# YosanoLoveButton.net
KiCad netlist of a schematic drawn in EAGLE
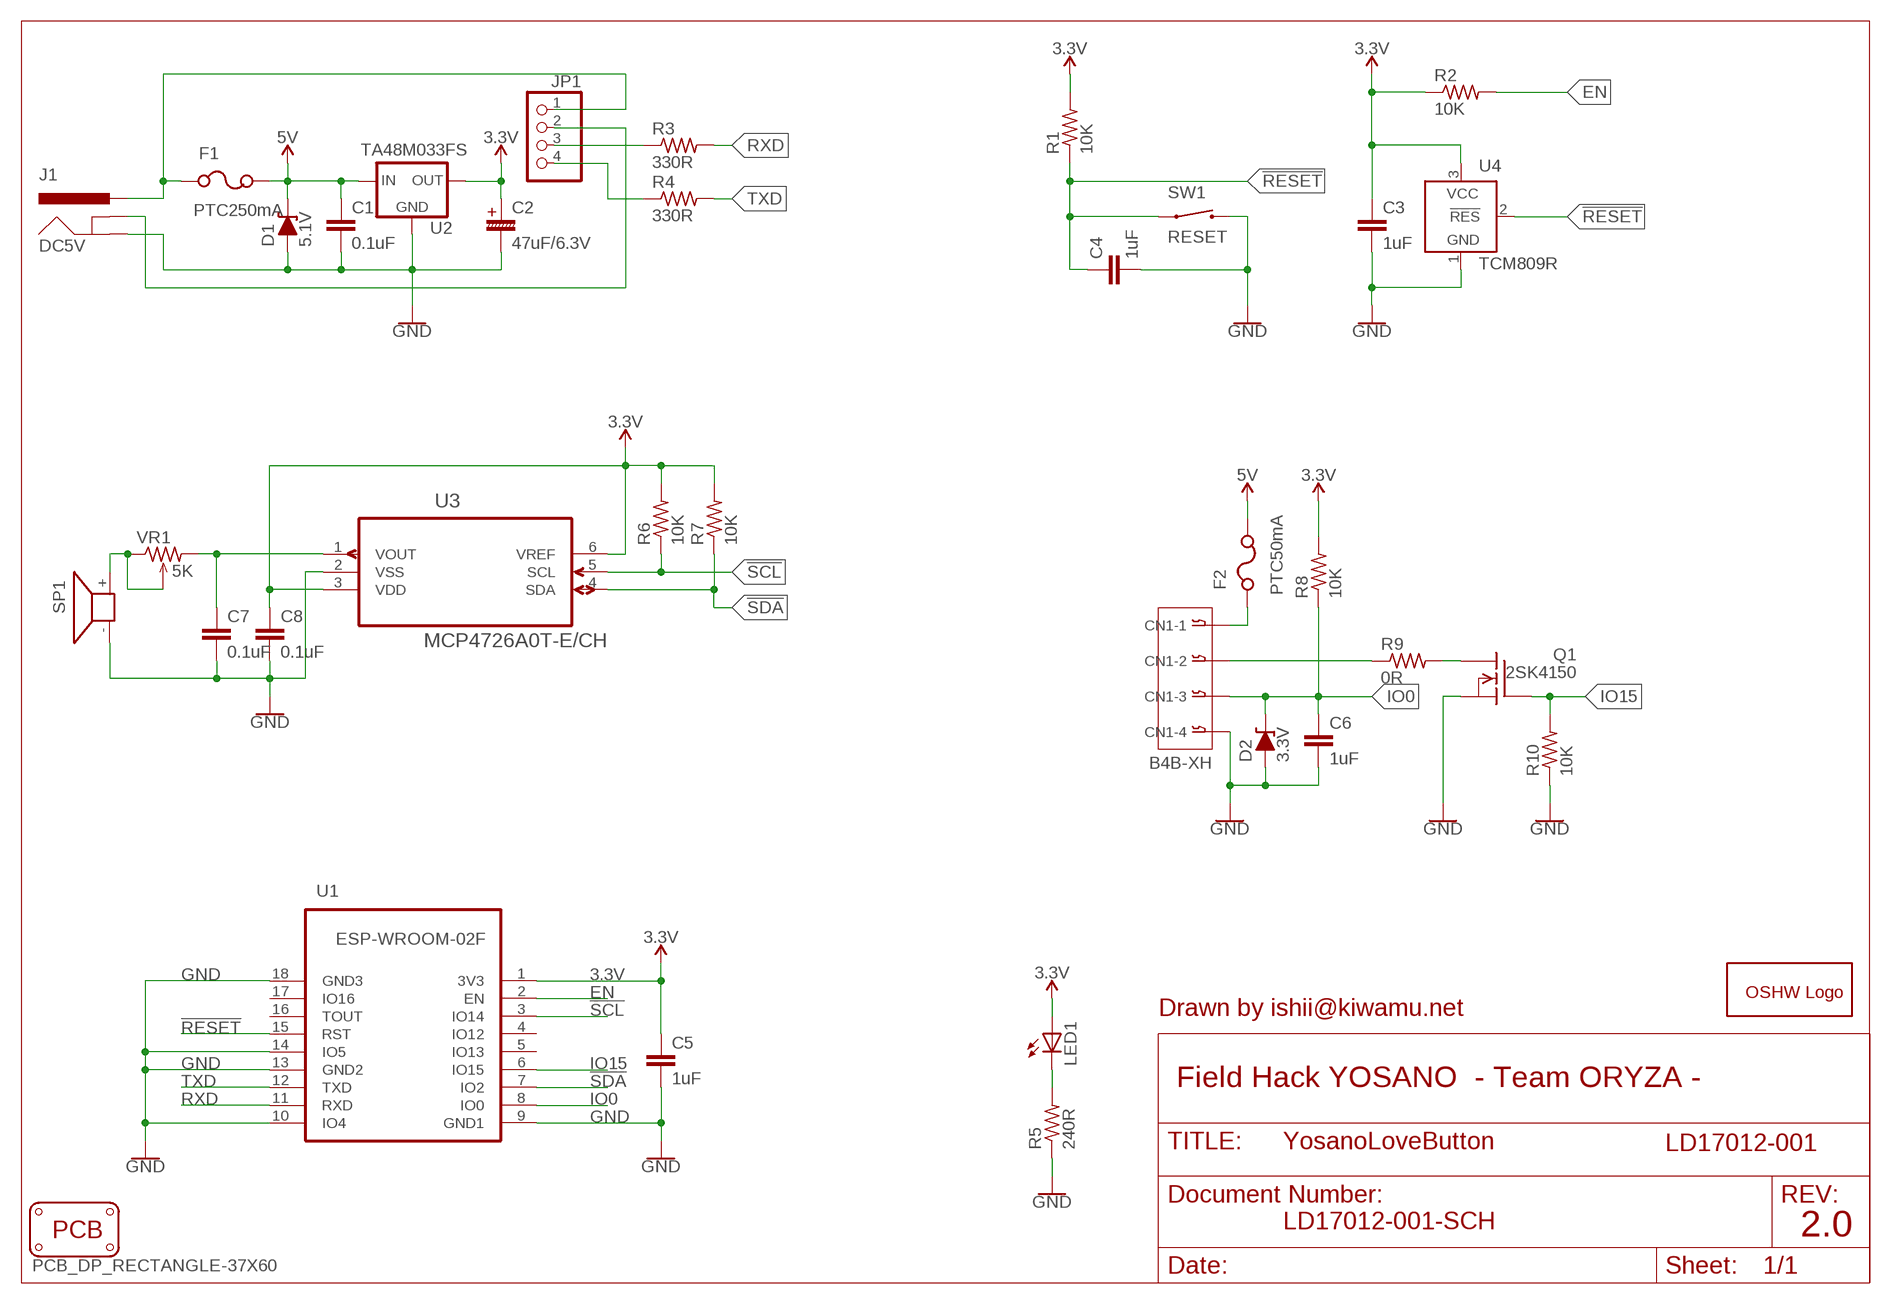
[diagram p0: schematic, sheet 1]

(export (version "E")
  (design (tool "Eeschema 10.0.6"))
  (components
    (comp (ref "C1")
      (value "0.1uF")
      (footprint "eagle-import:C5B2.5")
      (fields (field (name "MF") "株式会社村田製作所(muRata)") (field (name "MPN") "RDER72E104K2K1H03B"))
      (libsource (lib "eagle-import") (part "C5/2.5"))
    )
    (comp (ref "C2")
      (value "47uF/6.3V")
      (footprint "eagle-import:E2,0-5")
      (fields (field (name "MF") "東信工業") (field (name "MPN") "0JUTCX470M"))
      (libsource (lib "eagle-import") (part "C-PR-2,0X5"))
    )
    (comp (ref "C3")
      (value "1uF")
      (footprint "eagle-import:C5B2.5")
      (fields (field (name "MF") "株式会社村田製作所(muRata)") (field (name "MPN") "RDER71H105K2K1H03B"))
      (libsource (lib "eagle-import") (part "C5/2.5"))
    )
    (comp (ref "C4")
      (value "1uF")
      (footprint "eagle-import:C5B2.5")
      (fields (field (name "MF") "株式会社村田製作所(muRata)") (field (name "MPN") "RDER71H105K2K1H03B"))
      (libsource (lib "eagle-import") (part "C5/2.5"))
    )
    (comp (ref "C5")
      (value "1uF")
      (footprint "eagle-import:C5B2.5")
      (fields (field (name "MF") "株式会社村田製作所(muRata)") (field (name "MPN") "RDER71H105K2K1H03B"))
      (libsource (lib "eagle-import") (part "C5/2.5"))
    )
    (comp (ref "C6")
      (value "1uF")
      (footprint "eagle-import:C5B2.5")
      (fields (field (name "MF") "株式会社村田製作所(muRata)") (field (name "MPN") "RDER71H105K2K1H03B"))
      (libsource (lib "eagle-import") (part "C5/2.5"))
    )
    (comp (ref "C7")
      (value "0.1uF")
      (footprint "eagle-import:C5B2.5")
      (fields (field (name "MF") "株式会社村田製作所(muRata)") (field (name "MPN") "RDER72E104K2K1H03B"))
      (libsource (lib "eagle-import") (part "C5/2.5"))
    )
    (comp (ref "C8")
      (value "0.1uF")
      (footprint "eagle-import:C5B2.5")
      (fields (field (name "MF") "株式会社村田製作所(muRata)") (field (name "MPN") "RDER72E104K2K1H03B"))
      (libsource (lib "eagle-import") (part "C5/2.5"))
    )
    (comp (ref "CN1")
      (value "B4B-XH")
      (footprint "eagle-import:B4B-XH")
      (fields (field (name "MF") "日本圧着端子製造(JST)") (field (name "MPN") "B4B-XH-A(LF)(SN)"))
      (libsource (lib "eagle-import") (part "04-JST-B4B-XH-A"))
    )
    (comp (ref "D1")
      (value "5.1V")
      (footprint "eagle-import:ZDIO-5-LD")
      (fields (field (name "MF") "PANJIT") (field (name "MPN") "GDZJ5.1B"))
      (libsource (lib "eagle-import") (part "ZENER-DIODEZD-5LD"))
    )
    (comp (ref "D2")
      (value "3.3V")
      (footprint "eagle-import:ZDIO-5-LD")
      (fields (field (name "MF") "PANJIT") (field (name "MPN") "GDZJ3.3B"))
      (libsource (lib "eagle-import") (part "ZENER-DIODEZD-5LD"))
    )
    (comp (ref "F1")
      (value "PTC250mA")
      (footprint "eagle-import:PTC-PTH")
      (fields (field (name "MF") "Tyco Electronics Corporation") (field (name "MPN") "RXEF005"))
      (libsource (lib "eagle-import") (part "PTCPTH"))
    )
    (comp (ref "F2")
      (value "PTC50mA")
      (footprint "eagle-import:PTC-PTH")
      (fields (field (name "MF") "Tyco Electronics Corporation") (field (name "MPN") "RXEF005"))
      (libsource (lib "eagle-import") (part "PTCPTH"))
    )
    (comp (ref "GOLD_ORB_SM1")
      (value "OSHWLOGOLOGO5MM")
      (footprint "eagle-import:OSHW_5MM")
      (libsource (lib "eagle-import") (part "OSHWLOGOLOGO5MM"))
    )
    (comp (ref "J1")
      (value "DC5V")
      (footprint "eagle-import:POWER_JACK_PTH")
      (fields (field (name "MF") "マル信無線電機株式会社") (field (name "MPN") "MJ-179P"))
      (libsource (lib "eagle-import") (part "POWER_JACK"))
    )
    (comp (ref "JP1")
      (value "PINHD-1X4")
      (footprint "eagle-import:1X04")
      (fields (field (name "MF") "Useconn Electronics Ltd.") (field (name "MPN") "PHA-1x4SG"))
      (libsource (lib "eagle-import") (part "PINHD-1X4"))
    )
    (comp (ref "LED1")
      (value "LED3MM")
      (footprint "eagle-import:LED3MM")
      (fields (field (name "MF") "OptoSupply") (field (name "MPN") "OSR5JA3Z74A"))
      (libsource (lib "eagle-import") (part "LED3MM"))
    )
    (comp (ref "PCB1")
      (value "PCB_DP_RECTANGLE-37X60")
      (footprint "eagle-import:DP6037_V1")
      (libsource (lib "eagle-import") (part "PCB_DP_RECTANGLE-37X60"))
    )
    (comp (ref "Q1")
      (value "2SK4150")
      (footprint "eagle-import:TO92")
      (fields (field (name "MF") "RENESAS") (field (name "MPN") "2SK4150TZ-E"))
      (libsource (lib "eagle-import") (part "2SK4150"))
    )
    (comp (ref "R1")
      (value "10K")
      (footprint "eagle-import:0204_5")
      (fields (field (name "MF") "タクマン") (field (name "MPN") "RD25SJ10K"))
      (libsource (lib "eagle-import") (part "R-US_0204/5"))
    )
    (comp (ref "R2")
      (value "10K")
      (footprint "eagle-import:0204_5")
      (fields (field (name "MF") "タクマン") (field (name "MPN") "RD25SJ10K"))
      (libsource (lib "eagle-import") (part "R-US_0204/5"))
    )
    (comp (ref "R3")
      (value "330R")
      (footprint "eagle-import:0204_5")
      (fields (field (name "MF") "タクマン") (field (name "MPN") "RD25SJ330R"))
      (libsource (lib "eagle-import") (part "R-US_0204/5"))
    )
    (comp (ref "R4")
      (value "330R")
      (footprint "eagle-import:0204_5")
      (fields (field (name "MF") "タクマン") (field (name "MPN") "RD25SJ300R"))
      (libsource (lib "eagle-import") (part "R-US_0204/5"))
    )
    (comp (ref "R5")
      (value "240R")
      (footprint "eagle-import:0204_5")
      (fields (field (name "MF") "タクマン") (field (name "MPN") "RD25SJ 240R"))
      (libsource (lib "eagle-import") (part "R-US_0204/5"))
    )
    (comp (ref "R6")
      (value "10K")
      (footprint "eagle-import:0204_5")
      (fields (field (name "MF") "タクマン") (field (name "MPN") "RD25SJ10K"))
      (libsource (lib "eagle-import") (part "R-US_0204/5"))
    )
    (comp (ref "R7")
      (value "10K")
      (footprint "eagle-import:0204_5")
      (fields (field (name "MF") "タクマン") (field (name "MPN") "RD25SJ10K"))
      (libsource (lib "eagle-import") (part "R-US_0204/5"))
    )
    (comp (ref "R8")
      (value "10K")
      (footprint "eagle-import:0204_5")
      (fields (field (name "MF") "タクマン") (field (name "MPN") "RD25SJ10K"))
      (libsource (lib "eagle-import") (part "R-US_0204/5"))
    )
    (comp (ref "R9")
      (value "0R")
      (footprint "eagle-import:0204_5")
      (fields (field (name "MF") "タクマン") (field (name "MPN") "RD25SP 0R"))
      (libsource (lib "eagle-import") (part "R-US_0204/5"))
    )
    (comp (ref "R10")
      (value "10K")
      (footprint "eagle-import:0204_5")
      (fields (field (name "MF") "タクマン") (field (name "MPN") "RD25SJ10K"))
      (libsource (lib "eagle-import") (part "R-US_0204/5"))
    )
    (comp (ref "SP1")
      (value "PKM13EPYH4000")
      (footprint "eagle-import:PKM13EPYH4000")
      (fields (field (name "MF") "muRata"))
      (libsource (lib "eagle-import") (part "PKM13EPYH4000"))
    )
    (comp (ref "SW1")
      (value "RESET")
      (footprint "eagle-import:TVBP06")
      (fields
        (field (name "MF") "Zhejiang Jianfu Electronics Co., Ltd")
        (field (name "MPN") "TVBP06-B043CB-B")
      )
      (libsource (lib "eagle-import") (part "TVBP06"))
    )
    (comp (ref "U1")
      (value "ESP-WROOM-02F")
      (footprint "eagle-import:FRONT-FACE")
      (fields (field (name "MF") "Espressif") (field (name "MPN") "ESP-WROOM-02"))
      (libsource (lib "eagle-import") (part "ESP-WROOM-02F"))
    )
    (comp (ref "U2")
      (value "TA48M033FS")
      (footprint "eagle-import:HSIP3")
      (fields (field (name "MF") "株式会社東芝セミコンダクター社(TOSHIBA)") (field (name "MPN") "TA48M033F(S Q)"))
      (libsource (lib "eagle-import") (part "TA48MS033F"))
    )
    (comp (ref "U3")
      (value "MCP4726A0T-E/CH")
      (footprint "eagle-import:SOT95P270X145-6N")
      (fields (field (name "MF") "Microchip") (field (name "MPN") "MCP4725A0T-E/CH"))
      (libsource (lib "eagle-import") (part "MCP4726A0T-E/CH"))
    )
    (comp (ref "U4")
      (value "TCM809R")
      (footprint "eagle-import:SOT23B-3")
      (fields (field (name "MF") "MICROCHIP") (field (name "MPN") "TCM809MENB713"))
      (libsource (lib "eagle-import") (part "TCM809"))
    )
    (comp (ref "VR1")
      (value "5K")
      (footprint "eagle-import:3362P")
      (fields (field (name "MF") "bourns"))
      (libsource (lib "eagle-import") (part "3362P"))
    )
  )
  (nets
    (net (code "1") (name "/~{RESET}") (class "Default")
      (node (ref "C4") (pin "1") (pinfunction "1_1") (pintype "passive"))
      (node (ref "R1") (pin "1") (pinfunction "1_1") (pintype "passive"))
      (node (ref "SW1") (pin "1") (pinfunction "1_1") (pintype "passive"))
      (node (ref "U1") (pin "15") (pinfunction "RST_15") (pintype "bidirectional"))
      (node (ref "U4") (pin "2") (pinfunction "~{RES}_2") (pintype "output"))
    )
    (net (code "2") (name "/~{SCL}") (class "Default")
      (node (ref "R6") (pin "1") (pinfunction "1_1") (pintype "passive"))
      (node (ref "U1") (pin "3") (pinfunction "IO14_3") (pintype "bidirectional"))
      (node (ref "U3") (pin "5") (pinfunction "SCL_5") (pintype "input"))
    )
    (net (code "3") (name "/~{SDA}") (class "Default")
      (node (ref "R7") (pin "1") (pinfunction "1_1") (pintype "passive"))
      (node (ref "U1") (pin "7") (pinfunction "IO2_7") (pintype "bidirectional"))
      (node (ref "U3") (pin "4") (pinfunction "SDA_4") (pintype "bidirectional"))
    )
    (net (code "4") (name "3.3V") (class "Default")
      (node (ref "C2") (pin "+") (pinfunction "+_+") (pintype "passive"))
      (node (ref "C3") (pin "1") (pinfunction "1_1") (pintype "passive"))
      (node (ref "C5") (pin "1") (pinfunction "1_1") (pintype "passive"))
      (node (ref "C8") (pin "1") (pinfunction "1_1") (pintype "passive"))
      (node (ref "LED1") (pin "A") (pinfunction "A_A") (pintype "passive"))
      (node (ref "R1") (pin "2") (pinfunction "2_2") (pintype "passive"))
      (node (ref "R2") (pin "1") (pinfunction "1_1") (pintype "passive"))
      (node (ref "R6") (pin "2") (pinfunction "2_2") (pintype "passive"))
      (node (ref "R7") (pin "2") (pinfunction "2_2") (pintype "passive"))
      (node (ref "R8") (pin "2") (pinfunction "2_2") (pintype "passive"))
      (node (ref "U1") (pin "1") (pinfunction "3V3_1") (pintype "power_in"))
      (node (ref "U2") (pin "P$2") (pinfunction "OUT_P$2") (pintype "passive"))
      (node (ref "U3") (pin "3") (pinfunction "VDD_3") (pintype "power_in"))
      (node (ref "U3") (pin "6") (pinfunction "VREF_6") (pintype "power_in"))
      (node (ref "U4") (pin "3") (pinfunction "VCC_3") (pintype "power_in"))
    )
    (net (code "5") (name "5V") (class "Default")
      (node (ref "C1") (pin "1") (pinfunction "1_1") (pintype "passive"))
      (node (ref "D1") (pin "C") (pinfunction "C_C") (pintype "passive"))
      (node (ref "F1") (pin "2") (pinfunction "2_2") (pintype "bidirectional"))
      (node (ref "F2") (pin "2") (pinfunction "2_2") (pintype "bidirectional"))
      (node (ref "U2") (pin "P$1") (pinfunction "IN_P$1") (pintype "input"))
    )
    (net (code "6") (name "EN") (class "Default")
      (node (ref "R2") (pin "2") (pinfunction "2_2") (pintype "passive"))
      (node (ref "U1") (pin "2") (pinfunction "EN_2") (pintype "bidirectional"))
    )
    (net (code "7") (name "GND") (class "Default")
      (node (ref "C1") (pin "2") (pinfunction "2_2") (pintype "passive"))
      (node (ref "C2") (pin "-") (pinfunction "-_-") (pintype "passive"))
      (node (ref "C3") (pin "2") (pinfunction "2_2") (pintype "passive"))
      (node (ref "C4") (pin "2") (pinfunction "2_2") (pintype "passive"))
      (node (ref "C5") (pin "2") (pinfunction "2_2") (pintype "passive"))
      (node (ref "C6") (pin "2") (pinfunction "2_2") (pintype "passive"))
      (node (ref "C7") (pin "2") (pinfunction "2_2") (pintype "passive"))
      (node (ref "C8") (pin "2") (pinfunction "2_2") (pintype "passive"))
      (node (ref "CN1") (pin "P$4") (pinfunction "1_P$4") (pintype "passive"))
      (node (ref "D1") (pin "A") (pinfunction "A_A") (pintype "passive"))
      (node (ref "D2") (pin "A") (pinfunction "A_A") (pintype "passive"))
      (node (ref "J1") (pin "GND") (pinfunction "GND_GND") (pintype "bidirectional"))
      (node (ref "Q1") (pin "1") (pinfunction "S_1") (pintype "passive"))
      (node (ref "R10") (pin "1") (pinfunction "1_1") (pintype "passive"))
      (node (ref "R5") (pin "1") (pinfunction "1_1") (pintype "passive"))
      (node (ref "SP1") (pin "-") (pinfunction "2_-") (pintype "passive"))
      (node (ref "SW1") (pin "2") (pinfunction "2_2") (pintype "passive"))
      (node (ref "U1") (pin "10") (pinfunction "IO4_10") (pintype "bidirectional"))
      (node (ref "U1") (pin "13") (pinfunction "GND2_13") (pintype "power_in"))
      (node (ref "U1") (pin "14") (pinfunction "IO5_14") (pintype "open_collector"))
      (node (ref "U1") (pin "18") (pinfunction "GND3_18") (pintype "power_in"))
      (node (ref "U1") (pin "9") (pinfunction "GND1_9") (pintype "power_in"))
      (node (ref "U2") (pin "P$3") (pinfunction "GND_P$3") (pintype "power_in"))
      (node (ref "U3") (pin "2") (pinfunction "VSS_2") (pintype "power_in"))
      (node (ref "U4") (pin "1") (pinfunction "GND_1") (pintype "power_in"))
    )
    (net (code "8") (name "IO0") (class "Default")
      (node (ref "C6") (pin "1") (pinfunction "1_1") (pintype "passive"))
      (node (ref "CN1") (pin "P$3") (pinfunction "1_P$3") (pintype "passive"))
      (node (ref "D2") (pin "C") (pinfunction "C_C") (pintype "passive"))
      (node (ref "R8") (pin "1") (pinfunction "1_1") (pintype "passive"))
      (node (ref "U1") (pin "8") (pinfunction "IO0_8") (pintype "bidirectional"))
    )
    (net (code "9") (name "IO15") (class "Default")
      (node (ref "Q1") (pin "2") (pinfunction "G_2") (pintype "passive"))
      (node (ref "R10") (pin "2") (pinfunction "2_2") (pintype "passive"))
      (node (ref "U1") (pin "6") (pinfunction "IO15_6") (pintype "bidirectional"))
    )
    (net (code "10") (name "Net-(CN1A-1)") (class "Default")
      (node (ref "CN1") (pin "P$1") (pinfunction "1_P$1") (pintype "passive"))
      (node (ref "F2") (pin "1") (pinfunction "1_1") (pintype "bidirectional"))
    )
    (net (code "11") (name "Net-(CN1B-1)") (class "Default")
      (node (ref "CN1") (pin "P$2") (pinfunction "1_P$2") (pintype "passive"))
      (node (ref "R9") (pin "1") (pinfunction "1_1") (pintype "passive"))
    )
    (net (code "12") (name "Net-(F1-Pad1)") (class "Default")
      (node (ref "F1") (pin "1") (pinfunction "1_1") (pintype "bidirectional"))
      (node (ref "J1") (pin "PWR") (pinfunction "PWR_PWR") (pintype "bidirectional"))
      (node (ref "JP1") (pin "1") (pinfunction "1_1") (pintype "passive"))
    )
    (net (code "13") (name "Net-(J1-PadGNDBREAK)") (class "Default")
      (node (ref "J1") (pin "GNDBREAK") (pinfunction "GNDBREAK_GNDBREAK") (pintype "bidirectional"))
      (node (ref "JP1") (pin "2") (pinfunction "2_2") (pintype "passive"))
    )
    (net (code "14") (name "Net-(JP1-Pad3)") (class "Default")
      (node (ref "JP1") (pin "3") (pinfunction "3_3") (pintype "passive"))
      (node (ref "R3") (pin "1") (pinfunction "1_1") (pintype "passive"))
    )
    (net (code "15") (name "Net-(JP1-Pad4)") (class "Default")
      (node (ref "JP1") (pin "4") (pinfunction "4_4") (pintype "passive"))
      (node (ref "R4") (pin "1") (pinfunction "1_1") (pintype "passive"))
    )
    (net (code "16") (name "Net-(LED1-C)") (class "Default")
      (node (ref "LED1") (pin "K") (pinfunction "C_K") (pintype "passive"))
      (node (ref "R5") (pin "2") (pinfunction "2_2") (pintype "passive"))
    )
    (net (code "17") (name "Net-(Q1-D)") (class "Default")
      (node (ref "Q1") (pin "3") (pinfunction "D_3") (pintype "passive"))
      (node (ref "R9") (pin "2") (pinfunction "2_2") (pintype "passive"))
    )
    (net (code "18") (name "Net-(SP1-1)") (class "Default")
      (node (ref "SP1") (pin "+") (pinfunction "1_+") (pintype "passive"))
      (node (ref "VR1") (pin "1") (pinfunction "1_1") (pintype "passive"))
      (node (ref "VR1") (pin "2") (pinfunction "2_2") (pintype "passive"))
    )
    (net (code "19") (name "Net-(U3-VOUT)") (class "Default")
      (node (ref "C7") (pin "1") (pinfunction "1_1") (pintype "passive"))
      (node (ref "U3") (pin "1") (pinfunction "VOUT_1") (pintype "output"))
      (node (ref "VR1") (pin "3") (pinfunction "3_3") (pintype "passive"))
    )
    (net (code "20") (name "RXD") (class "Default")
      (node (ref "R3") (pin "2") (pinfunction "2_2") (pintype "passive"))
      (node (ref "U1") (pin "11") (pinfunction "RXD_11") (pintype "bidirectional"))
    )
    (net (code "21") (name "TXD") (class "Default")
      (node (ref "R4") (pin "2") (pinfunction "2_2") (pintype "passive"))
      (node (ref "U1") (pin "12") (pinfunction "TXD_12") (pintype "bidirectional"))
    )
    (net (code "22") (name "unconnected-(U1-IO12-Pad4)") (class "Default")
      (node (ref "U1") (pin "4") (pinfunction "IO12_4") (pintype "bidirectional"))
    )
    (net (code "23") (name "unconnected-(U1-IO13-Pad5)") (class "Default")
      (node (ref "U1") (pin "5") (pinfunction "IO13_5") (pintype "bidirectional"))
    )
    (net (code "24") (name "unconnected-(U1-IO16-Pad17)") (class "Default")
      (node (ref "U1") (pin "17") (pinfunction "IO16_17") (pintype "bidirectional"))
    )
    (net (code "25") (name "unconnected-(U1-TOUT-Pad16)") (class "Default")
      (node (ref "U1") (pin "16") (pinfunction "TOUT_16") (pintype "bidirectional"))
    )
  )
)
